# Tapuino_1_4.net
KiCad netlist of a schematic drawn in EAGLE
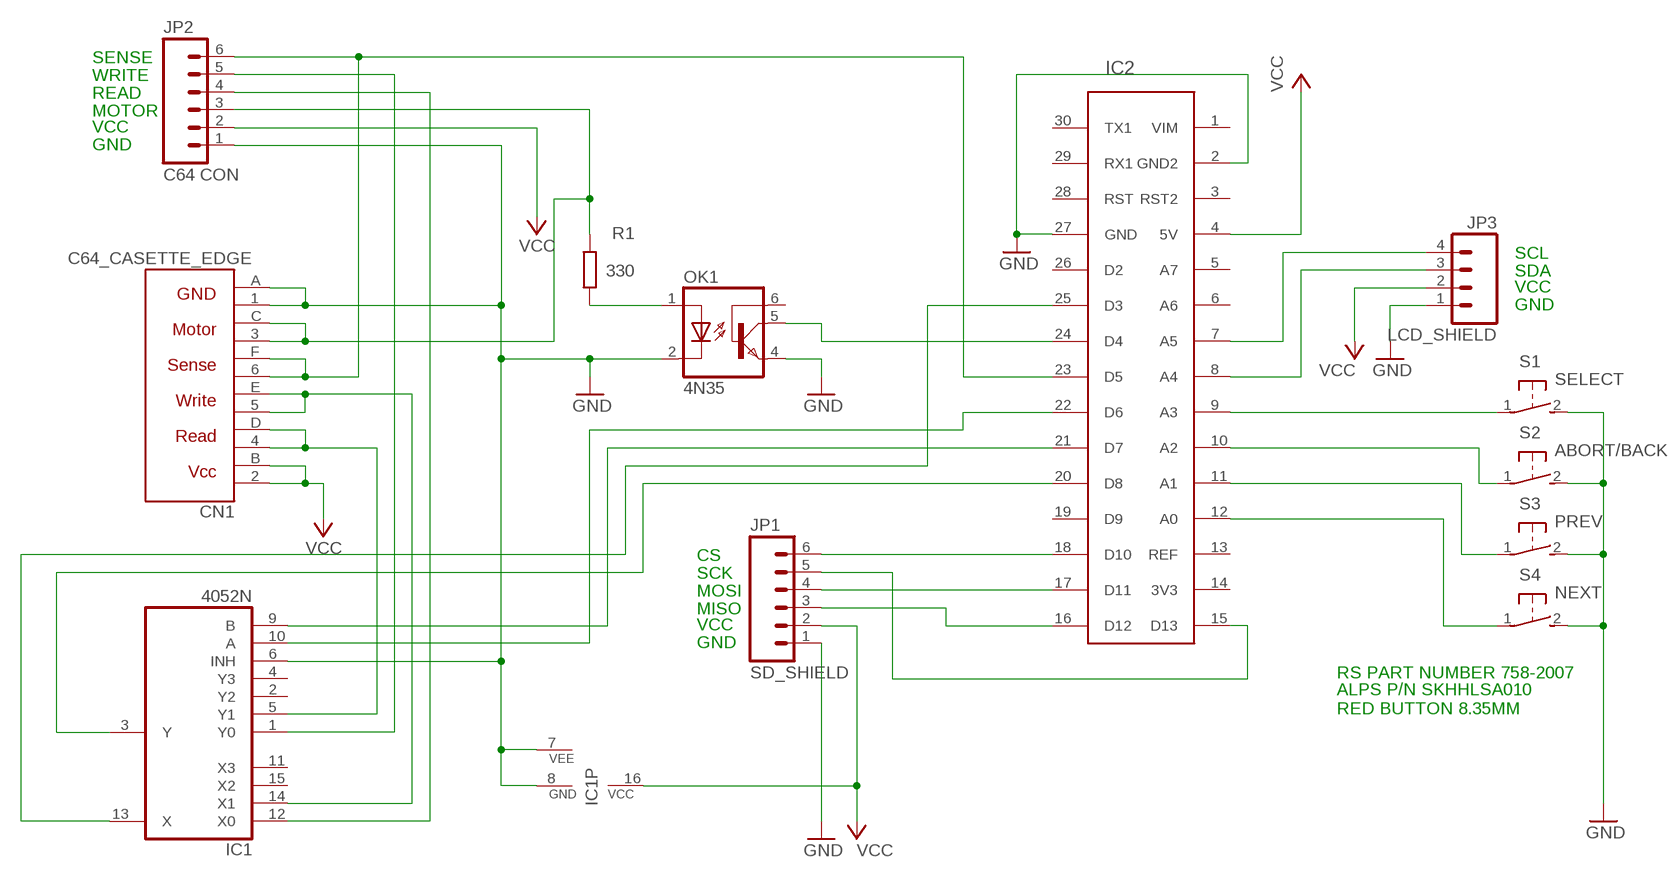
[diagram p0: schematic, sheet 1]

(export (version "E")
  (design (tool "Eeschema 10.0.6"))
  (components
    (comp (ref "CN1")
      (value "C64_CASETTE_EDGE")
      (footprint "eagle-import:C64_CASSETTE")
      (libsource (lib "eagle-import") (part "C64_CASETTE_EDGE"))
    )
    (comp (ref "IC1")
      (value "4052N")
      (footprint "eagle-import:DIL16")
      (libsource (lib "eagle-import") (part "4052N"))
    )
    (comp (ref "IC2")
      (value "ARDUINO_NANO_V3")
      (footprint "eagle-import:NANO_V3")
      (libsource (lib "eagle-import") (part "ARDUINO_NANO_V3"))
    )
    (comp (ref "JP1")
      (value "SD_SHIELD")
      (footprint "eagle-import:1X06_LOCK_LONGPADS")
      (libsource (lib "eagle-import") (part "M06LOCK_LONGPADS"))
    )
    (comp (ref "JP2")
      (value "C64 CON")
      (footprint "eagle-import:1X06_LOCK_LONGPADS")
      (libsource (lib "eagle-import") (part "M06LOCK_LONGPADS"))
    )
    (comp (ref "JP3")
      (value "LCD_SHIELD")
      (footprint "eagle-import:1X04_LOCK_LONGPADS")
      (libsource (lib "eagle-import") (part "M04LOCK_LONGPADS"))
    )
    (comp (ref "OK1")
      (value "4N35")
      (footprint "eagle-import:DIL06")
      (fields (field (name "MF") "FAIRCHILD SEMICONDUCTOR"))
      (libsource (lib "eagle-import") (part "4N35"))
    )
    (comp (ref "R1")
      (value "330")
      (footprint "eagle-import:0207_10")
      (libsource (lib "eagle-import") (part "R-EU_0207/10"))
    )
    (comp (ref "S1")
      (value "SELECT")
      (footprint "eagle-import:B3F-31XX")
      (fields (field (name "MPN") "B3F-3100"))
      (libsource (lib "eagle-import") (part "31-XX"))
    )
    (comp (ref "S2")
      (value "ABORT/BACK")
      (footprint "eagle-import:B3F-31XX")
      (fields (field (name "MPN") "B3F-3100"))
      (libsource (lib "eagle-import") (part "31-XX"))
    )
    (comp (ref "S3")
      (value "PREV")
      (footprint "eagle-import:B3F-31XX")
      (fields (field (name "MPN") "B3F-3100"))
      (libsource (lib "eagle-import") (part "31-XX"))
    )
    (comp (ref "S4")
      (value "NEXT")
      (footprint "eagle-import:B3F-31XX")
      (fields (field (name "MPN") "B3F-3100"))
      (libsource (lib "eagle-import") (part "31-XX"))
    )
  )
  (nets
    (net (code "1") (name "GND") (class "Default")
      (node (ref "CN1") (pin "1") (pinfunction "GND1_1") (pintype "power_in"))
      (node (ref "CN1") (pin "A") (pinfunction "GND2_A") (pintype "power_in"))
      (node (ref "IC1") (pin "6") (pinfunction "INH_6") (pintype "input"))
      (node (ref "IC1") (pin "7") (pinfunction "VEE_7") (pintype "power_in"))
      (node (ref "IC1") (pin "8") (pinfunction "GND_8") (pintype "power_in"))
      (node (ref "IC2") (pin "2") (pinfunction "GND2_2") (pintype "bidirectional"))
      (node (ref "IC2") (pin "27") (pinfunction "GND_27") (pintype "bidirectional"))
      (node (ref "JP1") (pin "1") (pinfunction "1_1") (pintype "passive"))
      (node (ref "JP2") (pin "1") (pinfunction "1_1") (pintype "passive"))
      (node (ref "JP3") (pin "1") (pinfunction "1_1") (pintype "passive"))
      (node (ref "OK1") (pin "2") (pinfunction "C_2") (pintype "passive"))
      (node (ref "OK1") (pin "4") (pinfunction "EMI_4") (pintype "passive"))
      (node (ref "S1") (pin "2") (pinfunction "S_2") (pintype "passive"))
      (node (ref "S2") (pin "2") (pinfunction "S_2") (pintype "passive"))
      (node (ref "S3") (pin "2") (pinfunction "S_2") (pintype "passive"))
      (node (ref "S4") (pin "2") (pinfunction "S_2") (pintype "passive"))
    )
    (net (code "2") (name "Net-(CN1-MOTOR1)") (class "Default")
      (node (ref "CN1") (pin "3") (pinfunction "MOTOR1_3") (pintype "output"))
      (node (ref "CN1") (pin "C") (pinfunction "MOTOR2_C") (pintype "output"))
      (node (ref "JP2") (pin "3") (pinfunction "3_3") (pintype "passive"))
      (node (ref "R1") (pin "2") (pinfunction "2_2") (pintype "passive"))
    )
    (net (code "3") (name "Net-(CN1-READ1)") (class "Default")
      (node (ref "CN1") (pin "4") (pinfunction "READ1_4") (pintype "output"))
      (node (ref "CN1") (pin "D") (pinfunction "READ2_D") (pintype "output"))
      (node (ref "IC1") (pin "5") (pinfunction "Y1_5") (pintype "bidirectional"))
    )
    (net (code "4") (name "Net-(CN1-SENSE1)") (class "Default")
      (node (ref "CN1") (pin "6") (pinfunction "SENSE1_6") (pintype "input"))
      (node (ref "CN1") (pin "F") (pinfunction "SENSE2_F") (pintype "input"))
      (node (ref "IC2") (pin "23") (pinfunction "D5_23") (pintype "bidirectional"))
      (node (ref "JP2") (pin "6") (pinfunction "6_6") (pintype "passive"))
    )
    (net (code "5") (name "Net-(CN1-WRITE1)") (class "Default")
      (node (ref "CN1") (pin "5") (pinfunction "WRITE1_5") (pintype "input"))
      (node (ref "CN1") (pin "E") (pinfunction "WRITE2_E") (pintype "input"))
      (node (ref "IC1") (pin "14") (pinfunction "X1_14") (pintype "bidirectional"))
    )
    (net (code "6") (name "Net-(IC1A-A)") (class "Default")
      (node (ref "IC1") (pin "10") (pinfunction "A_10") (pintype "input"))
      (node (ref "IC2") (pin "22") (pinfunction "D6_22") (pintype "bidirectional"))
    )
    (net (code "7") (name "Net-(IC1A-B)") (class "Default")
      (node (ref "IC1") (pin "9") (pinfunction "B_9") (pintype "input"))
      (node (ref "IC2") (pin "21") (pinfunction "D7_21") (pintype "bidirectional"))
    )
    (net (code "8") (name "Net-(IC1A-X)") (class "Default")
      (node (ref "IC1") (pin "13") (pinfunction "X_13") (pintype "bidirectional"))
      (node (ref "IC2") (pin "25") (pinfunction "D3_25") (pintype "bidirectional"))
    )
    (net (code "9") (name "Net-(IC1A-X0)") (class "Default")
      (node (ref "IC1") (pin "12") (pinfunction "X0_12") (pintype "bidirectional"))
      (node (ref "JP2") (pin "4") (pinfunction "4_4") (pintype "passive"))
    )
    (net (code "10") (name "Net-(IC1A-Y)") (class "Default")
      (node (ref "IC1") (pin "3") (pinfunction "Y_3") (pintype "bidirectional"))
      (node (ref "IC2") (pin "20") (pinfunction "D8_20") (pintype "bidirectional"))
    )
    (net (code "11") (name "Net-(IC1A-Y0)") (class "Default")
      (node (ref "IC1") (pin "1") (pinfunction "Y0_1") (pintype "bidirectional"))
      (node (ref "JP2") (pin "5") (pinfunction "5_5") (pintype "passive"))
    )
    (net (code "12") (name "Net-(IC2-A0)") (class "Default")
      (node (ref "IC2") (pin "12") (pinfunction "A0_12") (pintype "bidirectional"))
      (node (ref "S4") (pin "1") (pinfunction "P_1") (pintype "passive"))
    )
    (net (code "13") (name "Net-(IC2-A1)") (class "Default")
      (node (ref "IC2") (pin "11") (pinfunction "A1_11") (pintype "bidirectional"))
      (node (ref "S3") (pin "1") (pinfunction "P_1") (pintype "passive"))
    )
    (net (code "14") (name "Net-(IC2-A2)") (class "Default")
      (node (ref "IC2") (pin "10") (pinfunction "A2_10") (pintype "bidirectional"))
      (node (ref "S2") (pin "1") (pinfunction "P_1") (pintype "passive"))
    )
    (net (code "15") (name "Net-(IC2-A3)") (class "Default")
      (node (ref "IC2") (pin "9") (pinfunction "A3_9") (pintype "bidirectional"))
      (node (ref "S1") (pin "1") (pinfunction "P_1") (pintype "passive"))
    )
    (net (code "16") (name "Net-(IC2-A4)") (class "Default")
      (node (ref "IC2") (pin "8") (pinfunction "A4_8") (pintype "bidirectional"))
      (node (ref "JP3") (pin "3") (pinfunction "3_3") (pintype "passive"))
    )
    (net (code "17") (name "Net-(IC2-A5)") (class "Default")
      (node (ref "IC2") (pin "7") (pinfunction "A5_7") (pintype "bidirectional"))
      (node (ref "JP3") (pin "4") (pinfunction "4_4") (pintype "passive"))
    )
    (net (code "18") (name "Net-(IC2-D4)") (class "Default")
      (node (ref "IC2") (pin "24") (pinfunction "D4_24") (pintype "bidirectional"))
      (node (ref "OK1") (pin "5") (pinfunction "COL_5") (pintype "passive"))
    )
    (net (code "19") (name "Net-(IC2-D10)") (class "Default")
      (node (ref "IC2") (pin "18") (pinfunction "D10_18") (pintype "bidirectional"))
      (node (ref "JP1") (pin "6") (pinfunction "6_6") (pintype "passive"))
    )
    (net (code "20") (name "Net-(IC2-D11)") (class "Default")
      (node (ref "IC2") (pin "17") (pinfunction "D11_17") (pintype "bidirectional"))
      (node (ref "JP1") (pin "4") (pinfunction "4_4") (pintype "passive"))
    )
    (net (code "21") (name "Net-(IC2-D12)") (class "Default")
      (node (ref "IC2") (pin "16") (pinfunction "D12_16") (pintype "bidirectional"))
      (node (ref "JP1") (pin "3") (pinfunction "3_3") (pintype "passive"))
    )
    (net (code "22") (name "Net-(IC2-D13)") (class "Default")
      (node (ref "IC2") (pin "15") (pinfunction "D13_15") (pintype "bidirectional"))
      (node (ref "JP1") (pin "5") (pinfunction "5_5") (pintype "passive"))
    )
    (net (code "23") (name "Net-(OK1-A)") (class "Default")
      (node (ref "OK1") (pin "1") (pinfunction "A_1") (pintype "passive"))
      (node (ref "R1") (pin "1") (pinfunction "1_1") (pintype "passive"))
    )
    (net (code "24") (name "VCC") (class "Default")
      (node (ref "CN1") (pin "2") (pinfunction "VCC1_2") (pintype "power_in"))
      (node (ref "CN1") (pin "B") (pinfunction "VCC2_B") (pintype "power_in"))
      (node (ref "IC1") (pin "16") (pinfunction "VCC_16") (pintype "power_in"))
      (node (ref "IC2") (pin "4") (pinfunction "5V_4") (pintype "bidirectional"))
      (node (ref "JP1") (pin "2") (pinfunction "2_2") (pintype "passive"))
      (node (ref "JP2") (pin "2") (pinfunction "2_2") (pintype "passive"))
      (node (ref "JP3") (pin "2") (pinfunction "2_2") (pintype "passive"))
    )
    (net (code "25") (name "unconnected-(IC1A-X2-Pad15)") (class "Default")
      (node (ref "IC1") (pin "15") (pinfunction "X2_15") (pintype "bidirectional"))
    )
    (net (code "26") (name "unconnected-(IC1A-X3-Pad11)") (class "Default")
      (node (ref "IC1") (pin "11") (pinfunction "X3_11") (pintype "bidirectional"))
    )
    (net (code "27") (name "unconnected-(IC1A-Y2-Pad2)") (class "Default")
      (node (ref "IC1") (pin "2") (pinfunction "Y2_2") (pintype "bidirectional"))
    )
    (net (code "28") (name "unconnected-(IC1A-Y3-Pad4)") (class "Default")
      (node (ref "IC1") (pin "4") (pinfunction "Y3_4") (pintype "bidirectional"))
    )
    (net (code "29") (name "unconnected-(IC2-3V3-Pad14)") (class "Default")
      (node (ref "IC2") (pin "14") (pinfunction "3V3_14") (pintype "bidirectional"))
    )
    (net (code "30") (name "unconnected-(IC2-A6-Pad6)") (class "Default")
      (node (ref "IC2") (pin "6") (pinfunction "A6_6") (pintype "bidirectional"))
    )
    (net (code "31") (name "unconnected-(IC2-A7-Pad5)") (class "Default")
      (node (ref "IC2") (pin "5") (pinfunction "A7_5") (pintype "bidirectional"))
    )
    (net (code "32") (name "unconnected-(IC2-D2-Pad26)") (class "Default")
      (node (ref "IC2") (pin "26") (pinfunction "D2_26") (pintype "bidirectional"))
    )
    (net (code "33") (name "unconnected-(IC2-D9-Pad19)") (class "Default")
      (node (ref "IC2") (pin "19") (pinfunction "D9_19") (pintype "bidirectional"))
    )
    (net (code "34") (name "unconnected-(IC2-REF-Pad13)") (class "Default")
      (node (ref "IC2") (pin "13") (pinfunction "REF_13") (pintype "bidirectional"))
    )
    (net (code "35") (name "unconnected-(IC2-RST-Pad28)") (class "Default")
      (node (ref "IC2") (pin "28") (pinfunction "RST_28") (pintype "bidirectional"))
    )
    (net (code "36") (name "unconnected-(IC2-RST2-Pad3)") (class "Default")
      (node (ref "IC2") (pin "3") (pinfunction "RST2_3") (pintype "bidirectional"))
    )
    (net (code "37") (name "unconnected-(IC2-RX1-Pad29)") (class "Default")
      (node (ref "IC2") (pin "29") (pinfunction "RX1_29") (pintype "bidirectional"))
    )
    (net (code "38") (name "unconnected-(IC2-TX1-Pad30)") (class "Default")
      (node (ref "IC2") (pin "30") (pinfunction "TX1_30") (pintype "bidirectional"))
    )
    (net (code "39") (name "unconnected-(IC2-VIM-Pad1)") (class "Default")
      (node (ref "IC2") (pin "1") (pinfunction "VIM_1") (pintype "bidirectional"))
    )
    (net (code "40") (name "unconnected-(OK1-BAS-Pad6)") (class "Default")
      (node (ref "OK1") (pin "6") (pinfunction "BAS_6") (pintype "passive"))
    )
  )
)
